# 612_jetracer_appendbord.net
KiCad netlist of a schematic drawn in EAGLE
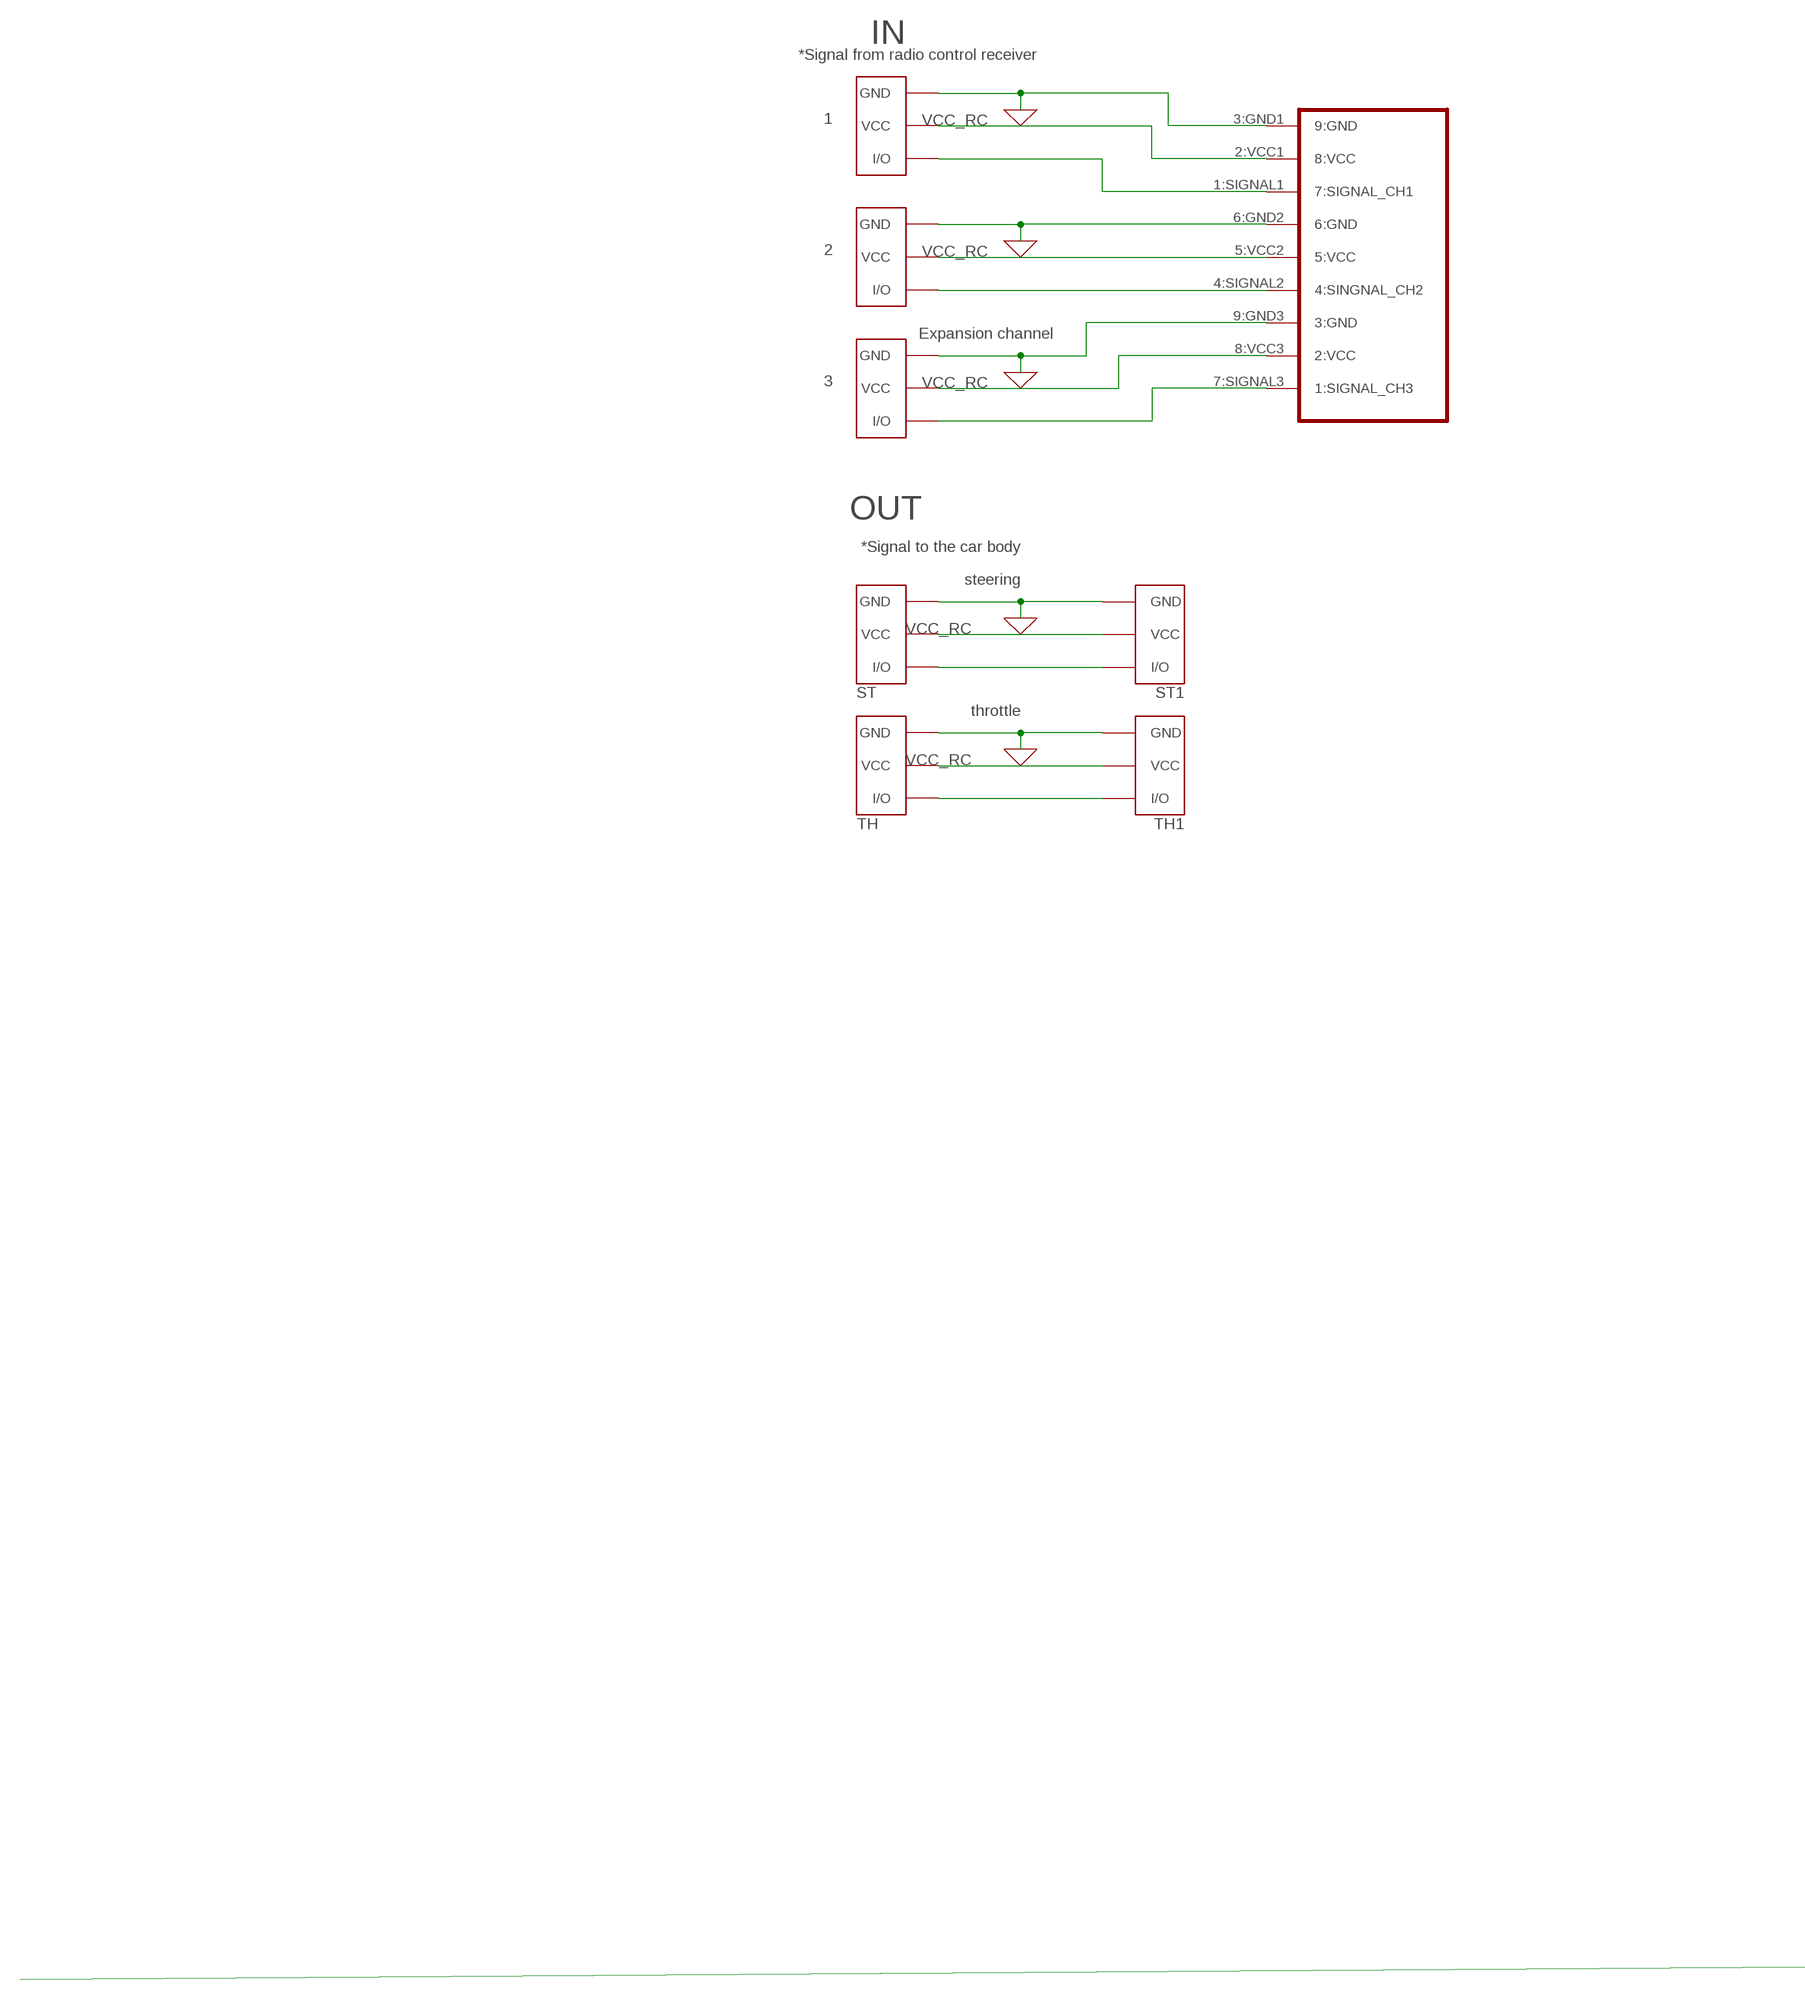
[diagram p0: schematic, sheet 1, part 1 of 2]
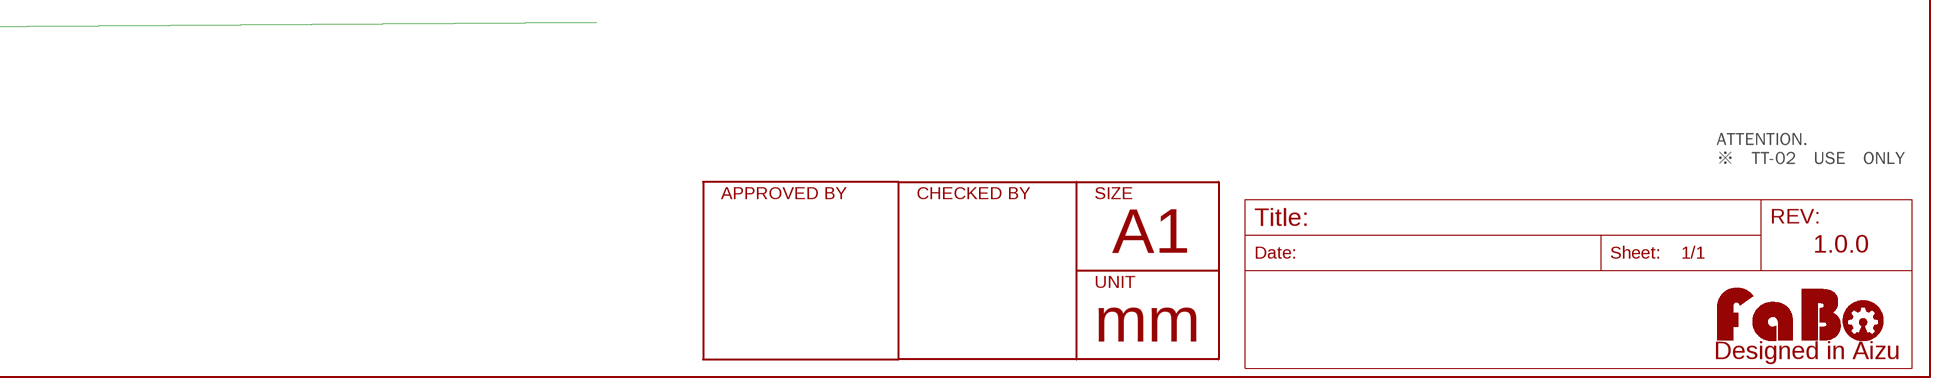
[diagram p1: schematic, sheet 1, part 2 of 2]

(export (version "E")
  (design (tool "Eeschema 10.0.6"))
  (components
    (comp (ref "1")
      (value "FABO_BRICK_3PIN-HEADER")
      (footprint "eagle-import:FABO_BRICK_3PIN_HEADER")
      (libsource (lib "eagle-import") (part "FABO_BRICK_3PIN-HEADER"))
    )
    (comp (ref "2")
      (value "FABO_BRICK_3PIN-HEADER")
      (footprint "eagle-import:FABO_BRICK_3PIN_HEADER")
      (libsource (lib "eagle-import") (part "FABO_BRICK_3PIN-HEADER"))
    )
    (comp (ref "3")
      (value "FABO_BRICK_3PIN-HEADER")
      (footprint "eagle-import:FABO_BRICK_3PIN_HEADER")
      (libsource (lib "eagle-import") (part "FABO_BRICK_3PIN-HEADER"))
    )
    (comp (ref "ST")
      (value "FABO_BRICK_3PIN-HEADER")
      (footprint "eagle-import:FABO_BRICK_3PIN_HEADER")
      (libsource (lib "eagle-import") (part "FABO_BRICK_3PIN-HEADER"))
    )
    (comp (ref "ST1")
      (value "FABO_BRICK_3PIN-HEADER")
      (footprint "eagle-import:FABO_BRICK_3PIN_HEADER")
      (libsource (lib "eagle-import") (part "FABO_BRICK_3PIN-HEADER"))
    )
    (comp (ref "TH")
      (value "FABO_BRICK_3PIN-HEADER")
      (footprint "eagle-import:FABO_BRICK_3PIN_HEADER")
      (libsource (lib "eagle-import") (part "FABO_BRICK_3PIN-HEADER"))
    )
    (comp (ref "TH1")
      (value "FABO_BRICK_3PIN-HEADER")
      (footprint "eagle-import:FABO_BRICK_3PIN_HEADER")
      (libsource (lib "eagle-import") (part "FABO_BRICK_3PIN-HEADER"))
    )
    (comp (ref "U$1")
      (value "RC_9PIN_OUTIN")
      (footprint "eagle-import:PNHEADER_2.54_SMT_9PIN_RC_TT01_02")
      (libsource (lib "eagle-import") (part "RC_9PIN_OUTIN"))
    )
    (comp (ref "U$5")
      (value "LOGO_FABO-M")
      (footprint "eagle-import:LOGO_FABO_MS")
      (libsource (lib "eagle-import") (part "LOGO_FABO-M"))
    )
  )
  (nets
    (net (code "1") (name "/VCC_RC") (class "Default")
      (node (ref "1") (pin "VCC") (pinfunction "VCC_VCC") (pintype "bidirectional"))
      (node (ref "2") (pin "VCC") (pinfunction "VCC_VCC") (pintype "bidirectional"))
      (node (ref "3") (pin "VCC") (pinfunction "VCC_VCC") (pintype "bidirectional"))
      (node (ref "ST") (pin "VCC") (pinfunction "VCC_VCC") (pintype "bidirectional"))
      (node (ref "ST1") (pin "VCC") (pinfunction "VCC_VCC") (pintype "bidirectional"))
      (node (ref "TH") (pin "VCC") (pinfunction "VCC_VCC") (pintype "bidirectional"))
      (node (ref "TH1") (pin "VCC") (pinfunction "VCC_VCC") (pintype "bidirectional"))
      (node (ref "U$1") (pin "2:VCC1") (pinfunction "8:VCC_2:VCC1") (pintype "bidirectional"))
      (node (ref "U$1") (pin "5:VCC2") (pinfunction "5:VCC_5:VCC2") (pintype "bidirectional"))
      (node (ref "U$1") (pin "8:VCC3") (pinfunction "2:VCC_8:VCC3") (pintype "bidirectional"))
    )
    (net (code "2") (name "GND") (class "Default")
      (node (ref "1") (pin "GND") (pinfunction "GND_GND") (pintype "bidirectional"))
      (node (ref "2") (pin "GND") (pinfunction "GND_GND") (pintype "bidirectional"))
      (node (ref "3") (pin "GND") (pinfunction "GND_GND") (pintype "bidirectional"))
      (node (ref "ST") (pin "GND") (pinfunction "GND_GND") (pintype "bidirectional"))
      (node (ref "ST1") (pin "GND") (pinfunction "GND_GND") (pintype "bidirectional"))
      (node (ref "TH") (pin "GND") (pinfunction "GND_GND") (pintype "bidirectional"))
      (node (ref "TH1") (pin "GND") (pinfunction "GND_GND") (pintype "bidirectional"))
      (node (ref "U$1") (pin "3:GND1") (pinfunction "9:GND_3:GND1") (pintype "bidirectional"))
      (node (ref "U$1") (pin "6:GND2") (pinfunction "6:GND_6:GND2") (pintype "bidirectional"))
      (node (ref "U$1") (pin "9:GND3") (pinfunction "3:GND_9:GND3") (pintype "bidirectional"))
    )
    (net (code "3") (name "Net-(ST-PadI{slash}O)") (class "Default")
      (node (ref "ST") (pin "I/O") (pinfunction "I/O_I/O") (pintype "bidirectional"))
      (node (ref "ST1") (pin "I/O") (pinfunction "I/O_I/O") (pintype "bidirectional"))
    )
    (net (code "4") (name "Net-(TH-PadI{slash}O)") (class "Default")
      (node (ref "TH") (pin "I/O") (pinfunction "I/O_I/O") (pintype "bidirectional"))
      (node (ref "TH1") (pin "I/O") (pinfunction "I/O_I/O") (pintype "bidirectional"))
    )
    (net (code "5") (name "Net-(U$1-1:SIGNAL_CH3)") (class "Default")
      (node (ref "3") (pin "I/O") (pinfunction "I/O_I/O") (pintype "bidirectional"))
      (node (ref "U$1") (pin "7:SIGNAL3") (pinfunction "1:SIGNAL_CH3_7:SIGNAL3") (pintype "bidirectional"))
    )
    (net (code "6") (name "Net-(U$1-4:SINGNAL_CH2)") (class "Default")
      (node (ref "2") (pin "I/O") (pinfunction "I/O_I/O") (pintype "bidirectional"))
      (node (ref "U$1") (pin "4:SIGNAL2") (pinfunction "4:SINGNAL_CH2_4:SIGNAL2") (pintype "bidirectional"))
    )
    (net (code "7") (name "Net-(U$1-7:SIGNAL_CH1)") (class "Default")
      (node (ref "1") (pin "I/O") (pinfunction "I/O_I/O") (pintype "bidirectional"))
      (node (ref "U$1") (pin "1:SIGNAL1") (pinfunction "7:SIGNAL_CH1_1:SIGNAL1") (pintype "bidirectional"))
    )
  )
)
